# ADC_Array.net
KiCad netlist of a schematic drawn in Altium Designer
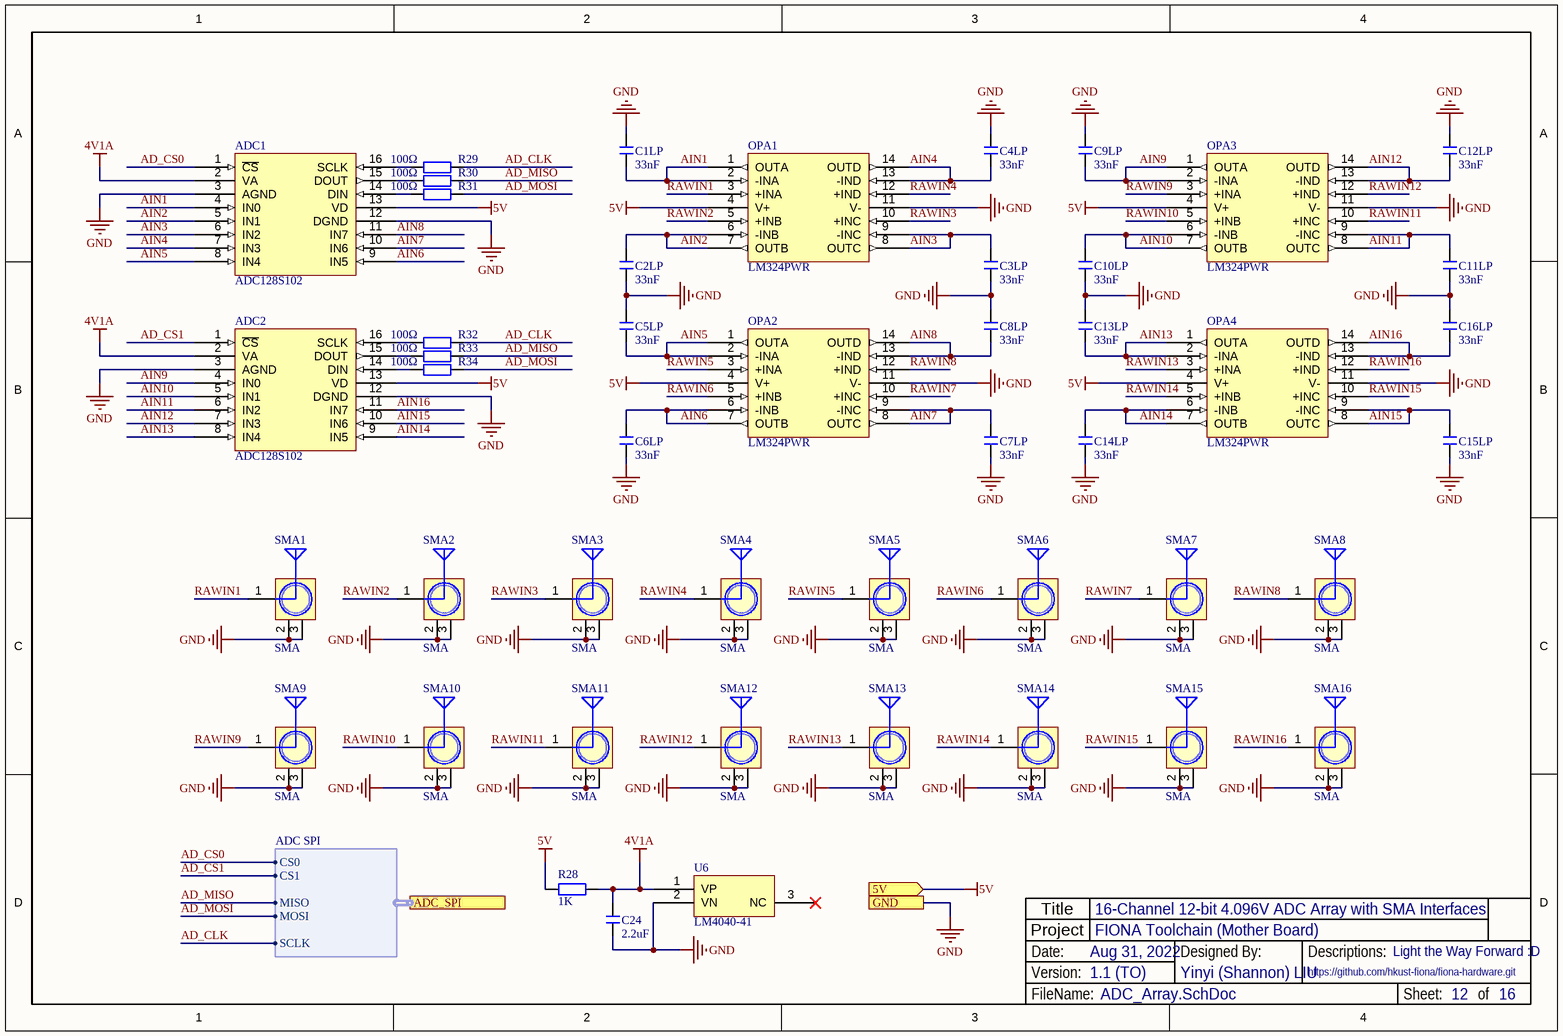
[diagram p0: ADC_Array.SchDoc]

(export (version "E")
  (design (tool "Eeschema 10.0.6"))
  (components
    (comp (ref "ADC1")
      (value "ADC128S102")
      (footprint "TSSOP16_N")
      (description "TI 12-bit Oct-channel ADC \r\nC179666")
      (libsource (lib "CustomizedComponents") (part "ADC128S102"))
    )
    (comp (ref "ADC2")
      (value "ADC128S102")
      (footprint "TSSOP16_N")
      (description "TI 12-bit Oct-channel ADC \r\nC179666")
      (libsource (lib "CustomizedComponents") (part "ADC128S102"))
    )
    (comp (ref "C1LP")
      (value "33nF")
      (footprint "C 0402_L")
      (description "贴片电容")
      (libsource (lib "0.1 - 电阻-电容-电感") (part "C"))
    )
    (comp (ref "C2LP")
      (value "33nF")
      (footprint "C 0402_L")
      (description "贴片电容")
      (libsource (lib "0.1 - 电阻-电容-电感") (part "C"))
    )
    (comp (ref "C3LP")
      (value "33nF")
      (footprint "C 0402_L")
      (description "贴片电容")
      (libsource (lib "0.1 - 电阻-电容-电感") (part "C"))
    )
    (comp (ref "C4LP")
      (value "33nF")
      (footprint "C 0402_L")
      (description "贴片电容")
      (libsource (lib "0.1 - 电阻-电容-电感") (part "C"))
    )
    (comp (ref "C5LP")
      (value "33nF")
      (footprint "C 0402_L")
      (description "贴片电容")
      (libsource (lib "0.1 - 电阻-电容-电感") (part "C"))
    )
    (comp (ref "C6LP")
      (value "33nF")
      (footprint "C 0402_L")
      (description "贴片电容")
      (libsource (lib "0.1 - 电阻-电容-电感") (part "C"))
    )
    (comp (ref "C7LP")
      (value "33nF")
      (footprint "C 0402_L")
      (description "贴片电容")
      (libsource (lib "0.1 - 电阻-电容-电感") (part "C"))
    )
    (comp (ref "C8LP")
      (value "33nF")
      (footprint "C 0402_L")
      (description "贴片电容")
      (libsource (lib "0.1 - 电阻-电容-电感") (part "C"))
    )
    (comp (ref "C9LP")
      (value "33nF")
      (footprint "C 0402_L")
      (description "贴片电容")
      (libsource (lib "0.1 - 电阻-电容-电感") (part "C"))
    )
    (comp (ref "C10LP")
      (value "33nF")
      (footprint "C 0402_L")
      (description "贴片电容")
      (libsource (lib "0.1 - 电阻-电容-电感") (part "C"))
    )
    (comp (ref "C11LP")
      (value "33nF")
      (footprint "C 0402_L")
      (description "贴片电容")
      (libsource (lib "0.1 - 电阻-电容-电感") (part "C"))
    )
    (comp (ref "C12LP")
      (value "33nF")
      (footprint "C 0402_L")
      (description "贴片电容")
      (libsource (lib "0.1 - 电阻-电容-电感") (part "C"))
    )
    (comp (ref "C13LP")
      (value "33nF")
      (footprint "C 0402_L")
      (description "贴片电容")
      (libsource (lib "0.1 - 电阻-电容-电感") (part "C"))
    )
    (comp (ref "C14LP")
      (value "33nF")
      (footprint "C 0402_L")
      (description "贴片电容")
      (libsource (lib "0.1 - 电阻-电容-电感") (part "C"))
    )
    (comp (ref "C15LP")
      (value "33nF")
      (footprint "C 0402_L")
      (description "贴片电容")
      (libsource (lib "0.1 - 电阻-电容-电感") (part "C"))
    )
    (comp (ref "C16LP")
      (value "33nF")
      (footprint "C 0402_L")
      (description "贴片电容")
      (libsource (lib "0.1 - 电阻-电容-电感") (part "C"))
    )
    (comp (ref "C24")
      (value "2.2uF")
      (footprint "C 0805_L")
      (description "贴片电容")
      (libsource (lib "0.1 - 电阻-电容-电感") (part "C"))
    )
    (comp (ref "OPA1")
      (value "LM324PWR")
      (footprint "TSSOP-14")
      (description "Quad-channel Operational Amplifier")
      (libsource (lib "CustomizedComponents") (part "OPA4197IPWR"))
    )
    (comp (ref "OPA2")
      (value "LM324PWR")
      (footprint "TSSOP-14")
      (description "Quad-channel Operational Amplifier")
      (libsource (lib "CustomizedComponents") (part "OPA4197IPWR"))
    )
    (comp (ref "OPA3")
      (value "LM324PWR")
      (footprint "TSSOP-14")
      (description "Quad-channel Operational Amplifier")
      (libsource (lib "CustomizedComponents") (part "OPA4197IPWR"))
    )
    (comp (ref "OPA4")
      (value "LM324PWR")
      (footprint "TSSOP-14")
      (description "Quad-channel Operational Amplifier")
      (libsource (lib "CustomizedComponents") (part "OPA4197IPWR"))
    )
    (comp (ref "R28")
      (value "1K")
      (footprint "R 0805_L")
      (description "贴片电阻 \r\n*LCID: C2907295")
      (fields (field (name "版权归属") "来自淘宝 ID：黄晶宝石"))
      (libsource (lib "0.1 - 电阻-电容-电感") (part "R"))
    )
    (comp (ref "R29")
      (value "100Ω")
      (footprint "R 0603_L")
      (description "贴片电阻")
      (fields (field (name "版权归属") "来自淘宝 ID：黄晶宝石"))
      (libsource (lib "0.1 - 电阻-电容-电感") (part "R"))
    )
    (comp (ref "R30")
      (value "100Ω")
      (footprint "R 0603_L")
      (description "贴片电阻")
      (fields (field (name "版权归属") "来自淘宝 ID：黄晶宝石"))
      (libsource (lib "0.1 - 电阻-电容-电感") (part "R"))
    )
    (comp (ref "R31")
      (value "100Ω")
      (footprint "R 0603_L")
      (description "贴片电阻")
      (fields (field (name "版权归属") "来自淘宝 ID：黄晶宝石"))
      (libsource (lib "0.1 - 电阻-电容-电感") (part "R"))
    )
    (comp (ref "R32")
      (value "100Ω")
      (footprint "R 0603_L")
      (description "贴片电阻")
      (fields (field (name "版权归属") "来自淘宝 ID：黄晶宝石"))
      (libsource (lib "0.1 - 电阻-电容-电感") (part "R"))
    )
    (comp (ref "R33")
      (value "100Ω")
      (footprint "R 0603_L")
      (description "贴片电阻")
      (fields (field (name "版权归属") "来自淘宝 ID：黄晶宝石"))
      (libsource (lib "0.1 - 电阻-电容-电感") (part "R"))
    )
    (comp (ref "R34")
      (value "100Ω")
      (footprint "R 0603_L")
      (description "贴片电阻")
      (fields (field (name "版权归属") "来自淘宝 ID：黄晶宝石"))
      (libsource (lib "0.1 - 电阻-电容-电感") (part "R"))
    )
    (comp (ref "SMA1")
      (value "SMA")
      (footprint "SMA_FR")
      (description "SMA-2.4G射频天线接口")
      (fields (field (name "版权归属") "封装库来自淘宝 ID：黄晶宝石"))
      (libsource (lib "0.8 - 以太网-音频-USB插座") (part "SMA"))
    )
    (comp (ref "SMA2")
      (value "SMA")
      (footprint "SMA_FR")
      (description "SMA-2.4G射频天线接口")
      (fields (field (name "版权归属") "封装库来自淘宝 ID：黄晶宝石"))
      (libsource (lib "0.8 - 以太网-音频-USB插座") (part "SMA"))
    )
    (comp (ref "SMA3")
      (value "SMA")
      (footprint "SMA_FR")
      (description "SMA-2.4G射频天线接口")
      (fields (field (name "版权归属") "封装库来自淘宝 ID：黄晶宝石"))
      (libsource (lib "0.8 - 以太网-音频-USB插座") (part "SMA"))
    )
    (comp (ref "SMA4")
      (value "SMA")
      (footprint "SMA_FR")
      (description "SMA-2.4G射频天线接口")
      (fields (field (name "版权归属") "封装库来自淘宝 ID：黄晶宝石"))
      (libsource (lib "0.8 - 以太网-音频-USB插座") (part "SMA"))
    )
    (comp (ref "SMA5")
      (value "SMA")
      (footprint "SMA_FR")
      (description "SMA-2.4G射频天线接口")
      (fields (field (name "版权归属") "封装库来自淘宝 ID：黄晶宝石"))
      (libsource (lib "0.8 - 以太网-音频-USB插座") (part "SMA"))
    )
    (comp (ref "SMA6")
      (value "SMA")
      (footprint "SMA_FR")
      (description "SMA-2.4G射频天线接口")
      (fields (field (name "版权归属") "封装库来自淘宝 ID：黄晶宝石"))
      (libsource (lib "0.8 - 以太网-音频-USB插座") (part "SMA"))
    )
    (comp (ref "SMA7")
      (value "SMA")
      (footprint "SMA_FR")
      (description "SMA-2.4G射频天线接口")
      (fields (field (name "版权归属") "封装库来自淘宝 ID：黄晶宝石"))
      (libsource (lib "0.8 - 以太网-音频-USB插座") (part "SMA"))
    )
    (comp (ref "SMA8")
      (value "SMA")
      (footprint "SMA_FR")
      (description "SMA-2.4G射频天线接口")
      (fields (field (name "版权归属") "封装库来自淘宝 ID：黄晶宝石"))
      (libsource (lib "0.8 - 以太网-音频-USB插座") (part "SMA"))
    )
    (comp (ref "SMA9")
      (value "SMA")
      (footprint "SMA_FR")
      (description "SMA-2.4G射频天线接口")
      (fields (field (name "版权归属") "封装库来自淘宝 ID：黄晶宝石"))
      (libsource (lib "0.8 - 以太网-音频-USB插座") (part "SMA"))
    )
    (comp (ref "SMA10")
      (value "SMA")
      (footprint "SMA_FR")
      (description "SMA-2.4G射频天线接口")
      (fields (field (name "版权归属") "封装库来自淘宝 ID：黄晶宝石"))
      (libsource (lib "0.8 - 以太网-音频-USB插座") (part "SMA"))
    )
    (comp (ref "SMA11")
      (value "SMA")
      (footprint "SMA_FR")
      (description "SMA-2.4G射频天线接口")
      (fields (field (name "版权归属") "封装库来自淘宝 ID：黄晶宝石"))
      (libsource (lib "0.8 - 以太网-音频-USB插座") (part "SMA"))
    )
    (comp (ref "SMA12")
      (value "SMA")
      (footprint "SMA_FR")
      (description "SMA-2.4G射频天线接口")
      (fields (field (name "版权归属") "封装库来自淘宝 ID：黄晶宝石"))
      (libsource (lib "0.8 - 以太网-音频-USB插座") (part "SMA"))
    )
    (comp (ref "SMA13")
      (value "SMA")
      (footprint "SMA_FR")
      (description "SMA-2.4G射频天线接口")
      (fields (field (name "版权归属") "封装库来自淘宝 ID：黄晶宝石"))
      (libsource (lib "0.8 - 以太网-音频-USB插座") (part "SMA"))
    )
    (comp (ref "SMA14")
      (value "SMA")
      (footprint "SMA_FR")
      (description "SMA-2.4G射频天线接口")
      (fields (field (name "版权归属") "封装库来自淘宝 ID：黄晶宝石"))
      (libsource (lib "0.8 - 以太网-音频-USB插座") (part "SMA"))
    )
    (comp (ref "SMA15")
      (value "SMA")
      (footprint "SMA_FR")
      (description "SMA-2.4G射频天线接口")
      (fields (field (name "版权归属") "封装库来自淘宝 ID：黄晶宝石"))
      (libsource (lib "0.8 - 以太网-音频-USB插座") (part "SMA"))
    )
    (comp (ref "SMA16")
      (value "SMA")
      (footprint "SMA_FR")
      (description "SMA-2.4G射频天线接口")
      (fields (field (name "版权归属") "封装库来自淘宝 ID：黄晶宝石"))
      (libsource (lib "0.8 - 以太网-音频-USB插座") (part "SMA"))
    )
    (comp (ref "U6")
      (value "LM4040-41")
      (footprint "SOT23-3")
      (description "Shunt Voltage Reference 4.096V")
      (libsource (lib "CustomizedComponents") (part "LM4040"))
    )
  )
  (nets
    (net (code "3") (name "/AD_CLK") (class "Default")
      (node (ref "R29") (pin "2") (pinfunction "2_2") (pintype "passive"))
      (node (ref "R32") (pin "2") (pinfunction "2_2") (pintype "passive"))
    )
    (net (code "4") (name "/AD_CS0") (class "Default")
      (node (ref "ADC1") (pin "1") (pinfunction "CS_1") (pintype "input"))
    )
    (net (code "5") (name "/AD_CS1") (class "Default")
      (node (ref "ADC2") (pin "1") (pinfunction "CS_1") (pintype "input"))
    )
    (net (code "6") (name "/AD_MISO") (class "Default")
      (node (ref "R30") (pin "2") (pinfunction "2_2") (pintype "passive"))
      (node (ref "R33") (pin "2") (pinfunction "2_2") (pintype "passive"))
    )
    (net (code "7") (name "/AD_MOSI") (class "Default")
      (node (ref "R31") (pin "2") (pinfunction "2_2") (pintype "passive"))
      (node (ref "R34") (pin "2") (pinfunction "2_2") (pintype "passive"))
    )
    (net (code "8") (name "/AIN1") (class "Default")
      (node (ref "ADC1") (pin "4") (pinfunction "IN0_4") (pintype "input"))
      (node (ref "C1LP") (pin "1") (pinfunction "1_1") (pintype "passive"))
      (node (ref "OPA1") (pin "1") (pinfunction "OUTA_1") (pintype "output"))
      (node (ref "OPA1") (pin "2") (pinfunction "-INA_2") (pintype "input"))
    )
    (net (code "9") (name "/AIN2") (class "Default")
      (node (ref "ADC1") (pin "5") (pinfunction "IN1_5") (pintype "input"))
      (node (ref "C2LP") (pin "2") (pinfunction "2_2") (pintype "passive"))
      (node (ref "OPA1") (pin "6") (pinfunction "-INB_6") (pintype "input"))
      (node (ref "OPA1") (pin "7") (pinfunction "OUTB_7") (pintype "output"))
    )
    (net (code "10") (name "/AIN3") (class "Default")
      (node (ref "ADC1") (pin "6") (pinfunction "IN2_6") (pintype "input"))
      (node (ref "C3LP") (pin "2") (pinfunction "2_2") (pintype "passive"))
      (node (ref "OPA1") (pin "8") (pinfunction "OUTC_8") (pintype "output"))
      (node (ref "OPA1") (pin "9") (pinfunction "-INC_9") (pintype "input"))
    )
    (net (code "11") (name "/AIN4") (class "Default")
      (node (ref "ADC1") (pin "7") (pinfunction "IN3_7") (pintype "input"))
      (node (ref "C4LP") (pin "1") (pinfunction "1_1") (pintype "passive"))
      (node (ref "OPA1") (pin "13") (pinfunction "-IND_13") (pintype "input"))
      (node (ref "OPA1") (pin "14") (pinfunction "OUTD_14") (pintype "output"))
    )
    (net (code "12") (name "/AIN5") (class "Default")
      (node (ref "ADC1") (pin "8") (pinfunction "IN4_8") (pintype "input"))
      (node (ref "C5LP") (pin "1") (pinfunction "1_1") (pintype "passive"))
      (node (ref "OPA2") (pin "1") (pinfunction "OUTA_1") (pintype "output"))
      (node (ref "OPA2") (pin "2") (pinfunction "-INA_2") (pintype "input"))
    )
    (net (code "13") (name "/AIN6") (class "Default")
      (node (ref "ADC1") (pin "9") (pinfunction "IN5_9") (pintype "input"))
      (node (ref "C6LP") (pin "2") (pinfunction "2_2") (pintype "passive"))
      (node (ref "OPA2") (pin "6") (pinfunction "-INB_6") (pintype "input"))
      (node (ref "OPA2") (pin "7") (pinfunction "OUTB_7") (pintype "output"))
    )
    (net (code "14") (name "/AIN7") (class "Default")
      (node (ref "ADC1") (pin "10") (pinfunction "IN6_10") (pintype "input"))
      (node (ref "C7LP") (pin "2") (pinfunction "2_2") (pintype "passive"))
      (node (ref "OPA2") (pin "8") (pinfunction "OUTC_8") (pintype "output"))
      (node (ref "OPA2") (pin "9") (pinfunction "-INC_9") (pintype "input"))
    )
    (net (code "15") (name "/AIN8") (class "Default")
      (node (ref "ADC1") (pin "11") (pinfunction "IN7_11") (pintype "input"))
      (node (ref "C8LP") (pin "1") (pinfunction "1_1") (pintype "passive"))
      (node (ref "OPA2") (pin "13") (pinfunction "-IND_13") (pintype "input"))
      (node (ref "OPA2") (pin "14") (pinfunction "OUTD_14") (pintype "output"))
    )
    (net (code "16") (name "/AIN9") (class "Default")
      (node (ref "ADC2") (pin "4") (pinfunction "IN0_4") (pintype "input"))
      (node (ref "C9LP") (pin "1") (pinfunction "1_1") (pintype "passive"))
      (node (ref "OPA3") (pin "1") (pinfunction "OUTA_1") (pintype "output"))
      (node (ref "OPA3") (pin "2") (pinfunction "-INA_2") (pintype "input"))
    )
    (net (code "17") (name "/AIN10") (class "Default")
      (node (ref "ADC2") (pin "5") (pinfunction "IN1_5") (pintype "input"))
      (node (ref "C10LP") (pin "2") (pinfunction "2_2") (pintype "passive"))
      (node (ref "OPA3") (pin "6") (pinfunction "-INB_6") (pintype "input"))
      (node (ref "OPA3") (pin "7") (pinfunction "OUTB_7") (pintype "output"))
    )
    (net (code "18") (name "/AIN11") (class "Default")
      (node (ref "ADC2") (pin "6") (pinfunction "IN2_6") (pintype "input"))
      (node (ref "C11LP") (pin "2") (pinfunction "2_2") (pintype "passive"))
      (node (ref "OPA3") (pin "8") (pinfunction "OUTC_8") (pintype "output"))
      (node (ref "OPA3") (pin "9") (pinfunction "-INC_9") (pintype "input"))
    )
    (net (code "19") (name "/AIN12") (class "Default")
      (node (ref "ADC2") (pin "7") (pinfunction "IN3_7") (pintype "input"))
      (node (ref "C12LP") (pin "1") (pinfunction "1_1") (pintype "passive"))
      (node (ref "OPA3") (pin "13") (pinfunction "-IND_13") (pintype "input"))
      (node (ref "OPA3") (pin "14") (pinfunction "OUTD_14") (pintype "output"))
    )
    (net (code "20") (name "/AIN13") (class "Default")
      (node (ref "ADC2") (pin "8") (pinfunction "IN4_8") (pintype "input"))
      (node (ref "C13LP") (pin "1") (pinfunction "1_1") (pintype "passive"))
      (node (ref "OPA4") (pin "1") (pinfunction "OUTA_1") (pintype "output"))
      (node (ref "OPA4") (pin "2") (pinfunction "-INA_2") (pintype "input"))
    )
    (net (code "21") (name "/AIN14") (class "Default")
      (node (ref "ADC2") (pin "9") (pinfunction "IN5_9") (pintype "input"))
      (node (ref "C14LP") (pin "2") (pinfunction "2_2") (pintype "passive"))
      (node (ref "OPA4") (pin "6") (pinfunction "-INB_6") (pintype "input"))
      (node (ref "OPA4") (pin "7") (pinfunction "OUTB_7") (pintype "output"))
    )
    (net (code "22") (name "/AIN15") (class "Default")
      (node (ref "ADC2") (pin "10") (pinfunction "IN6_10") (pintype "input"))
      (node (ref "C15LP") (pin "2") (pinfunction "2_2") (pintype "passive"))
      (node (ref "OPA4") (pin "8") (pinfunction "OUTC_8") (pintype "output"))
      (node (ref "OPA4") (pin "9") (pinfunction "-INC_9") (pintype "input"))
    )
    (net (code "23") (name "/AIN16") (class "Default")
      (node (ref "ADC2") (pin "11") (pinfunction "IN7_11") (pintype "input"))
      (node (ref "C16LP") (pin "1") (pinfunction "1_1") (pintype "passive"))
      (node (ref "OPA4") (pin "13") (pinfunction "-IND_13") (pintype "input"))
      (node (ref "OPA4") (pin "14") (pinfunction "OUTD_14") (pintype "output"))
    )
    (net (code "24") (name "/RAWIN1") (class "Default")
      (node (ref "OPA1") (pin "3") (pinfunction "+INA_3") (pintype "input"))
      (node (ref "SMA1") (pin "1") (pinfunction "ANT_1") (pintype "passive"))
    )
    (net (code "25") (name "/RAWIN2") (class "Default")
      (node (ref "OPA1") (pin "5") (pinfunction "+INB_5") (pintype "input"))
      (node (ref "SMA2") (pin "1") (pinfunction "ANT_1") (pintype "passive"))
    )
    (net (code "26") (name "/RAWIN3") (class "Default")
      (node (ref "OPA1") (pin "10") (pinfunction "+INC_10") (pintype "input"))
      (node (ref "SMA3") (pin "1") (pinfunction "ANT_1") (pintype "passive"))
    )
    (net (code "27") (name "/RAWIN4") (class "Default")
      (node (ref "OPA1") (pin "12") (pinfunction "+IND_12") (pintype "input"))
      (node (ref "SMA4") (pin "1") (pinfunction "ANT_1") (pintype "passive"))
    )
    (net (code "28") (name "/RAWIN5") (class "Default")
      (node (ref "OPA2") (pin "3") (pinfunction "+INA_3") (pintype "input"))
      (node (ref "SMA5") (pin "1") (pinfunction "ANT_1") (pintype "passive"))
    )
    (net (code "29") (name "/RAWIN6") (class "Default")
      (node (ref "OPA2") (pin "5") (pinfunction "+INB_5") (pintype "input"))
      (node (ref "SMA6") (pin "1") (pinfunction "ANT_1") (pintype "passive"))
    )
    (net (code "30") (name "/RAWIN7") (class "Default")
      (node (ref "OPA2") (pin "10") (pinfunction "+INC_10") (pintype "input"))
      (node (ref "SMA7") (pin "1") (pinfunction "ANT_1") (pintype "passive"))
    )
    (net (code "31") (name "/RAWIN8") (class "Default")
      (node (ref "OPA2") (pin "12") (pinfunction "+IND_12") (pintype "input"))
      (node (ref "SMA8") (pin "1") (pinfunction "ANT_1") (pintype "passive"))
    )
    (net (code "32") (name "/RAWIN9") (class "Default")
      (node (ref "OPA3") (pin "3") (pinfunction "+INA_3") (pintype "input"))
      (node (ref "SMA9") (pin "1") (pinfunction "ANT_1") (pintype "passive"))
    )
    (net (code "33") (name "/RAWIN10") (class "Default")
      (node (ref "OPA3") (pin "5") (pinfunction "+INB_5") (pintype "input"))
      (node (ref "SMA10") (pin "1") (pinfunction "ANT_1") (pintype "passive"))
    )
    (net (code "34") (name "/RAWIN11") (class "Default")
      (node (ref "OPA3") (pin "10") (pinfunction "+INC_10") (pintype "input"))
      (node (ref "SMA11") (pin "1") (pinfunction "ANT_1") (pintype "passive"))
    )
    (net (code "35") (name "/RAWIN12") (class "Default")
      (node (ref "OPA3") (pin "12") (pinfunction "+IND_12") (pintype "input"))
      (node (ref "SMA12") (pin "1") (pinfunction "ANT_1") (pintype "passive"))
    )
    (net (code "36") (name "/RAWIN13") (class "Default")
      (node (ref "OPA4") (pin "3") (pinfunction "+INA_3") (pintype "input"))
      (node (ref "SMA13") (pin "1") (pinfunction "ANT_1") (pintype "passive"))
    )
    (net (code "37") (name "/RAWIN14") (class "Default")
      (node (ref "OPA4") (pin "5") (pinfunction "+INB_5") (pintype "input"))
      (node (ref "SMA14") (pin "1") (pinfunction "ANT_1") (pintype "passive"))
    )
    (net (code "38") (name "/RAWIN15") (class "Default")
      (node (ref "OPA4") (pin "10") (pinfunction "+INC_10") (pintype "input"))
      (node (ref "SMA15") (pin "1") (pinfunction "ANT_1") (pintype "passive"))
    )
    (net (code "39") (name "/RAWIN16") (class "Default")
      (node (ref "OPA4") (pin "12") (pinfunction "+IND_12") (pintype "input"))
      (node (ref "SMA16") (pin "1") (pinfunction "ANT_1") (pintype "passive"))
    )
    (net (code "41") (name "4V1A") (class "Default")
      (node (ref "ADC1") (pin "2") (pinfunction "VA_2") (pintype "passive"))
      (node (ref "ADC2") (pin "2") (pinfunction "VA_2") (pintype "passive"))
      (node (ref "C24") (pin "1") (pinfunction "1_1") (pintype "passive"))
      (node (ref "R28") (pin "2") (pinfunction "2_2") (pintype "passive"))
      (node (ref "U6") (pin "1") (pinfunction "VP_1") (pintype "passive"))
    )
    (net (code "42") (name "5V") (class "Default")
      (node (ref "ADC1") (pin "13") (pinfunction "VD_13") (pintype "passive"))
      (node (ref "ADC2") (pin "13") (pinfunction "VD_13") (pintype "passive"))
      (node (ref "OPA1") (pin "4") (pinfunction "V+_4") (pintype "power_in"))
      (node (ref "OPA2") (pin "4") (pinfunction "V+_4") (pintype "power_in"))
      (node (ref "OPA3") (pin "4") (pinfunction "V+_4") (pintype "power_in"))
      (node (ref "OPA4") (pin "4") (pinfunction "V+_4") (pintype "power_in"))
      (node (ref "R28") (pin "1") (pinfunction "1_1") (pintype "passive"))
    )
    (net (code "43") (name "GND") (class "Default")
      (node (ref "ADC1") (pin "12") (pinfunction "DGND_12") (pintype "passive"))
      (node (ref "ADC1") (pin "3") (pinfunction "AGND_3") (pintype "passive"))
      (node (ref "ADC2") (pin "12") (pinfunction "DGND_12") (pintype "passive"))
      (node (ref "ADC2") (pin "3") (pinfunction "AGND_3") (pintype "passive"))
      (node (ref "C10LP") (pin "1") (pinfunction "1_1") (pintype "passive"))
      (node (ref "C11LP") (pin "1") (pinfunction "1_1") (pintype "passive"))
      (node (ref "C12LP") (pin "2") (pinfunction "2_2") (pintype "passive"))
      (node (ref "C13LP") (pin "2") (pinfunction "2_2") (pintype "passive"))
      (node (ref "C14LP") (pin "1") (pinfunction "1_1") (pintype "passive"))
      (node (ref "C15LP") (pin "1") (pinfunction "1_1") (pintype "passive"))
      (node (ref "C16LP") (pin "2") (pinfunction "2_2") (pintype "passive"))
      (node (ref "C1LP") (pin "2") (pinfunction "2_2") (pintype "passive"))
      (node (ref "C24") (pin "2") (pinfunction "2_2") (pintype "passive"))
      (node (ref "C2LP") (pin "1") (pinfunction "1_1") (pintype "passive"))
      (node (ref "C3LP") (pin "1") (pinfunction "1_1") (pintype "passive"))
      (node (ref "C4LP") (pin "2") (pinfunction "2_2") (pintype "passive"))
      (node (ref "C5LP") (pin "2") (pinfunction "2_2") (pintype "passive"))
      (node (ref "C6LP") (pin "1") (pinfunction "1_1") (pintype "passive"))
      (node (ref "C7LP") (pin "1") (pinfunction "1_1") (pintype "passive"))
      (node (ref "C8LP") (pin "2") (pinfunction "2_2") (pintype "passive"))
      (node (ref "C9LP") (pin "2") (pinfunction "2_2") (pintype "passive"))
      (node (ref "OPA1") (pin "11") (pinfunction "V-_11") (pintype "power_in"))
      (node (ref "OPA2") (pin "11") (pinfunction "V-_11") (pintype "power_in"))
      (node (ref "OPA3") (pin "11") (pinfunction "V-_11") (pintype "power_in"))
      (node (ref "OPA4") (pin "11") (pinfunction "V-_11") (pintype "power_in"))
      (node (ref "SMA1") (pin "2") (pinfunction "GND_2") (pintype "passive"))
      (node (ref "SMA1") (pin "3") (pinfunction "GND_3") (pintype "passive"))
      (node (ref "SMA10") (pin "2") (pinfunction "GND_2") (pintype "passive"))
      (node (ref "SMA10") (pin "3") (pinfunction "GND_3") (pintype "passive"))
      (node (ref "SMA11") (pin "2") (pinfunction "GND_2") (pintype "passive"))
      (node (ref "SMA11") (pin "3") (pinfunction "GND_3") (pintype "passive"))
      (node (ref "SMA12") (pin "2") (pinfunction "GND_2") (pintype "passive"))
      (node (ref "SMA12") (pin "3") (pinfunction "GND_3") (pintype "passive"))
      (node (ref "SMA13") (pin "2") (pinfunction "GND_2") (pintype "passive"))
      (node (ref "SMA13") (pin "3") (pinfunction "GND_3") (pintype "passive"))
      (node (ref "SMA14") (pin "2") (pinfunction "GND_2") (pintype "passive"))
      (node (ref "SMA14") (pin "3") (pinfunction "GND_3") (pintype "passive"))
      (node (ref "SMA15") (pin "2") (pinfunction "GND_2") (pintype "passive"))
      (node (ref "SMA15") (pin "3") (pinfunction "GND_3") (pintype "passive"))
      (node (ref "SMA16") (pin "2") (pinfunction "GND_2") (pintype "passive"))
      (node (ref "SMA16") (pin "3") (pinfunction "GND_3") (pintype "passive"))
      (node (ref "SMA2") (pin "2") (pinfunction "GND_2") (pintype "passive"))
      (node (ref "SMA2") (pin "3") (pinfunction "GND_3") (pintype "passive"))
      (node (ref "SMA3") (pin "2") (pinfunction "GND_2") (pintype "passive"))
      (node (ref "SMA3") (pin "3") (pinfunction "GND_3") (pintype "passive"))
      (node (ref "SMA4") (pin "2") (pinfunction "GND_2") (pintype "passive"))
      (node (ref "SMA4") (pin "3") (pinfunction "GND_3") (pintype "passive"))
      (node (ref "SMA5") (pin "2") (pinfunction "GND_2") (pintype "passive"))
      (node (ref "SMA5") (pin "3") (pinfunction "GND_3") (pintype "passive"))
      (node (ref "SMA6") (pin "2") (pinfunction "GND_2") (pintype "passive"))
      (node (ref "SMA6") (pin "3") (pinfunction "GND_3") (pintype "passive"))
      (node (ref "SMA7") (pin "2") (pinfunction "GND_2") (pintype "passive"))
      (node (ref "SMA7") (pin "3") (pinfunction "GND_3") (pintype "passive"))
      (node (ref "SMA8") (pin "2") (pinfunction "GND_2") (pintype "passive"))
      (node (ref "SMA8") (pin "3") (pinfunction "GND_3") (pintype "passive"))
      (node (ref "SMA9") (pin "2") (pinfunction "GND_2") (pintype "passive"))
      (node (ref "SMA9") (pin "3") (pinfunction "GND_3") (pintype "passive"))
      (node (ref "U6") (pin "2") (pinfunction "VN_2") (pintype "passive"))
    )
    (net (code "44") (name "Net-(ADC1-DIN)") (class "Default")
      (node (ref "ADC1") (pin "14") (pinfunction "DIN_14") (pintype "input"))
      (node (ref "R31") (pin "1") (pinfunction "1_1") (pintype "passive"))
    )
    (net (code "45") (name "Net-(ADC1-DOUT)") (class "Default")
      (node (ref "ADC1") (pin "15") (pinfunction "DOUT_15") (pintype "output"))
      (node (ref "R30") (pin "1") (pinfunction "1_1") (pintype "passive"))
    )
    (net (code "46") (name "Net-(ADC1-SCLK)") (class "Default")
      (node (ref "ADC1") (pin "16") (pinfunction "SCLK_16") (pintype "input"))
      (node (ref "R29") (pin "1") (pinfunction "1_1") (pintype "passive"))
    )
    (net (code "47") (name "Net-(ADC2-DIN)") (class "Default")
      (node (ref "ADC2") (pin "14") (pinfunction "DIN_14") (pintype "input"))
      (node (ref "R34") (pin "1") (pinfunction "1_1") (pintype "passive"))
    )
    (net (code "48") (name "Net-(ADC2-DOUT)") (class "Default")
      (node (ref "ADC2") (pin "15") (pinfunction "DOUT_15") (pintype "output"))
      (node (ref "R33") (pin "1") (pinfunction "1_1") (pintype "passive"))
    )
    (net (code "49") (name "Net-(ADC2-SCLK)") (class "Default")
      (node (ref "ADC2") (pin "16") (pinfunction "SCLK_16") (pintype "input"))
      (node (ref "R32") (pin "1") (pinfunction "1_1") (pintype "passive"))
    )
    (net (code "50") (name "unconnected-(U6-NC-Pad3)") (class "Default")
      (node (ref "U6") (pin "3") (pinfunction "NC_3") (pintype "passive+no_connect"))
    )
  )
)
